# POWER.net
KiCad netlist of a schematic drawn in Altium Designer
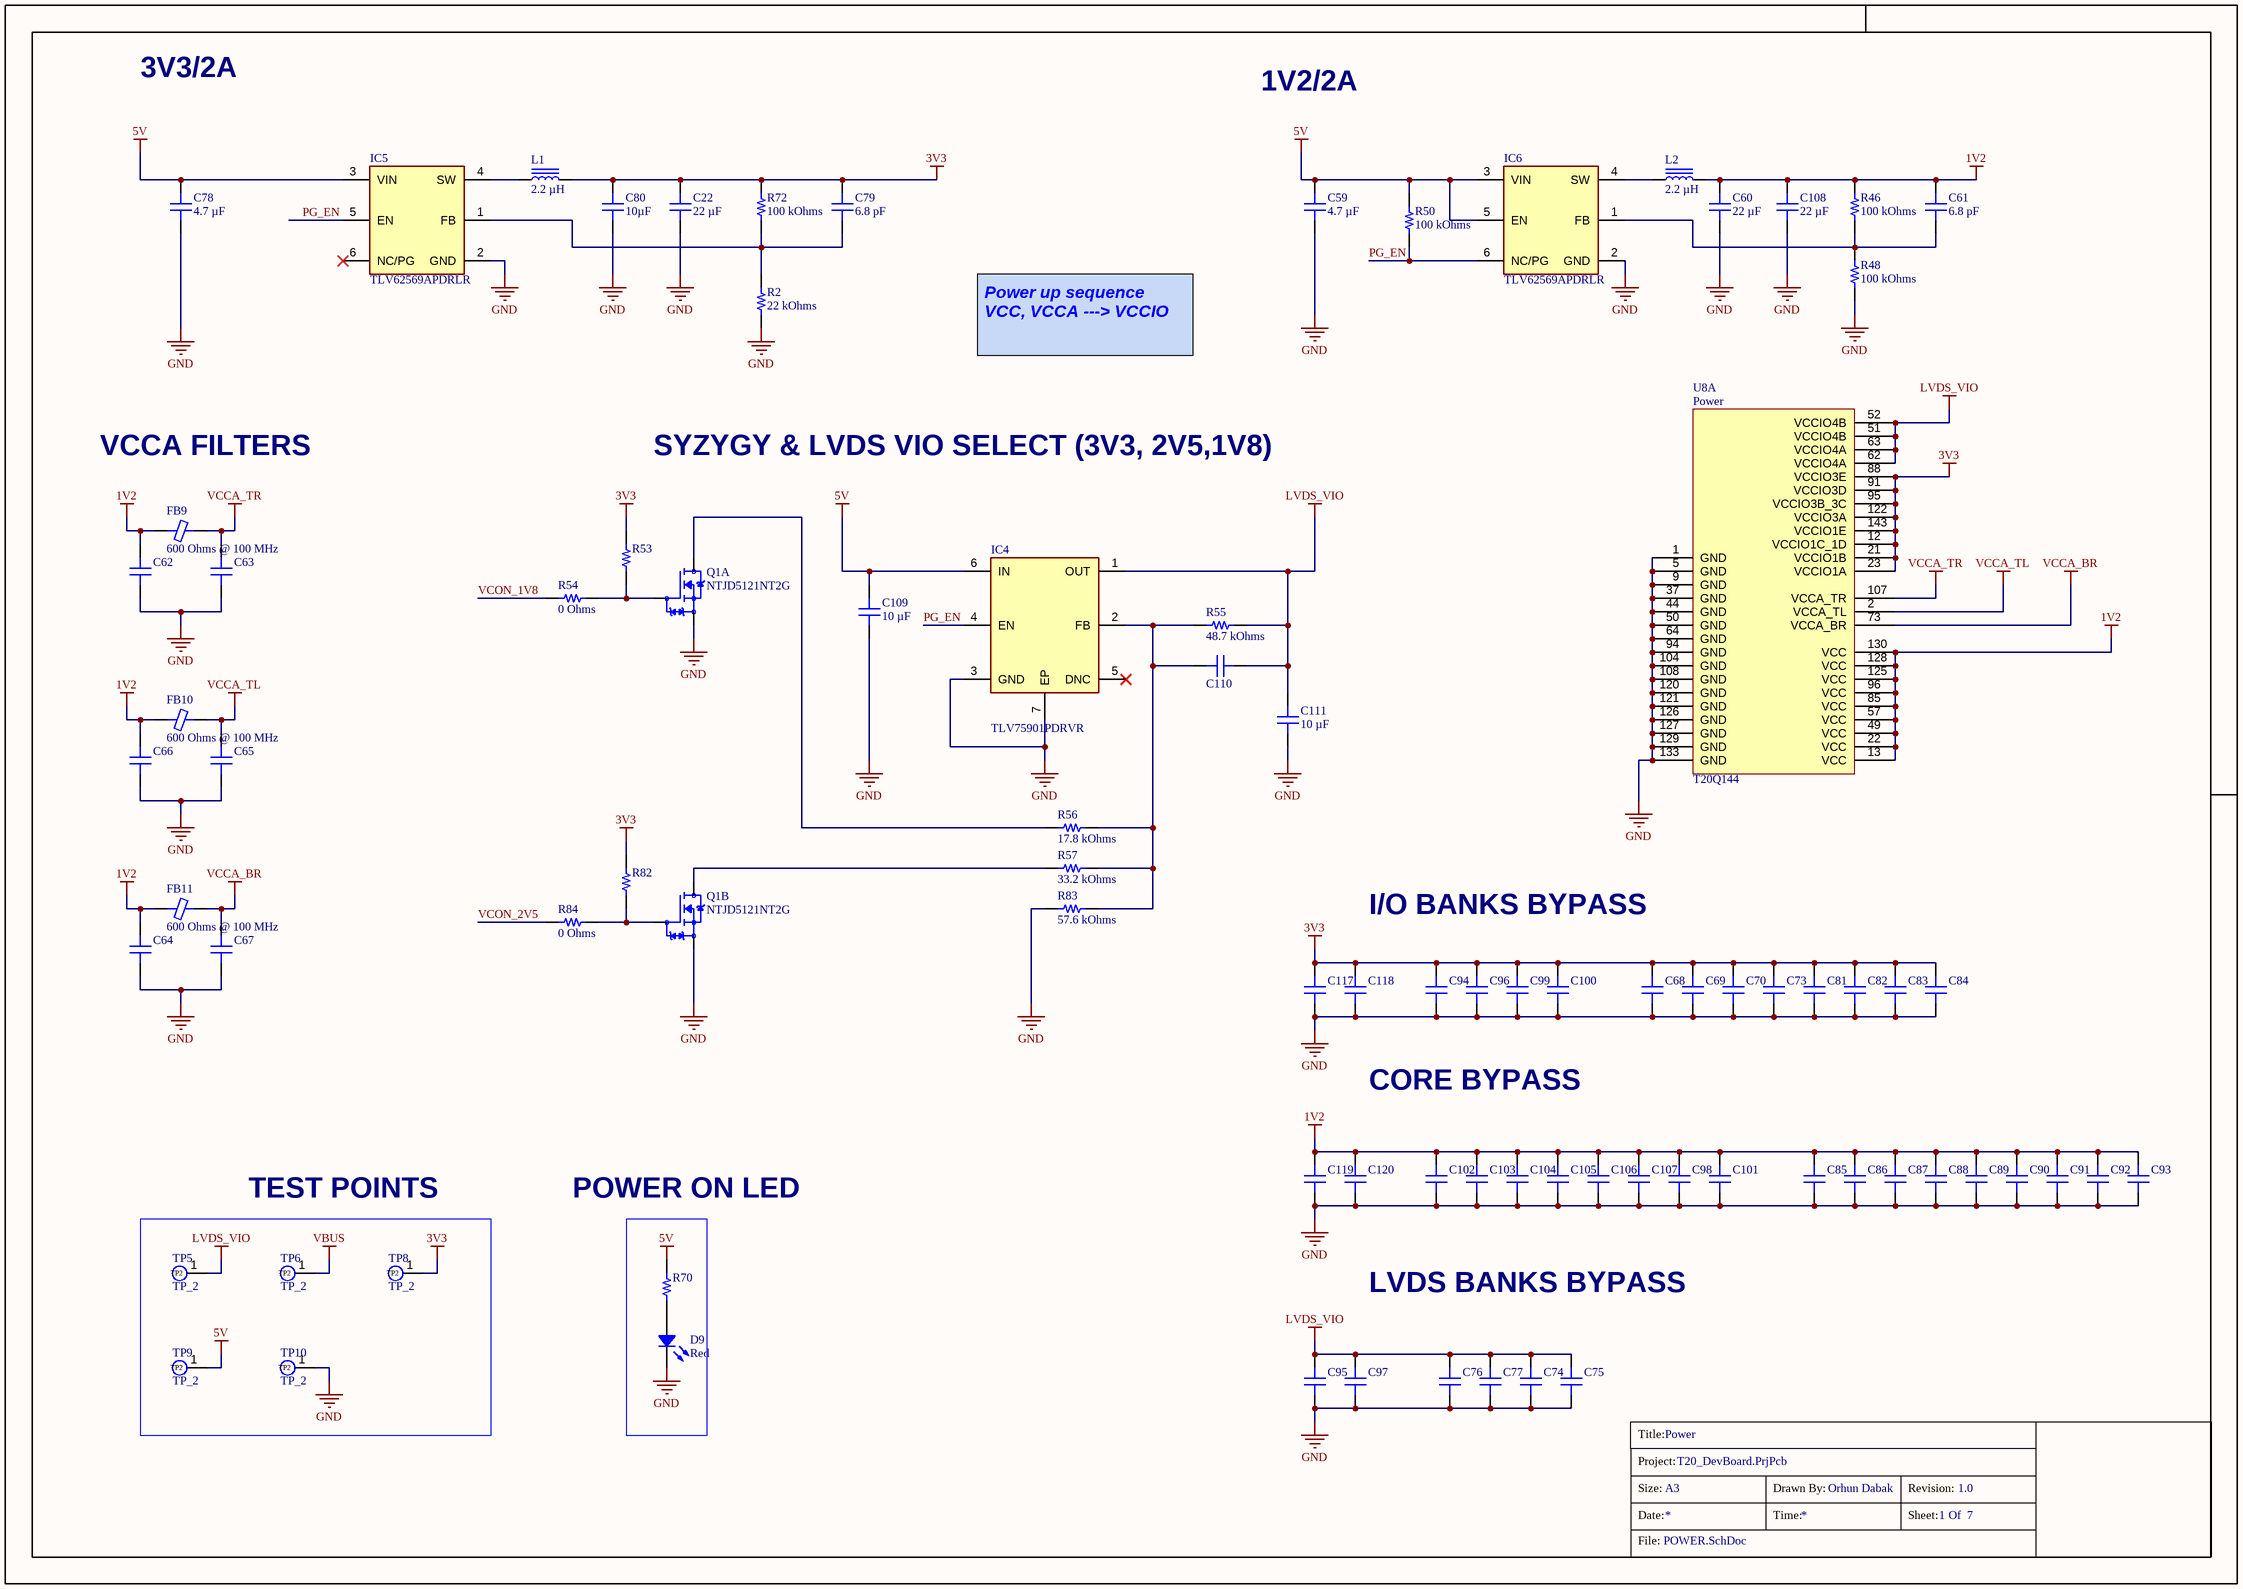
[diagram p0: POWER.SchDoc]

(export (version "E")
  (design (tool "Eeschema 10.0.6"))
  (components
    (comp (ref "C22")
      (value "22 µF")
      (footprint "CAP 0805_2012")
      (description "CAP CER 22UF 10V X5R 0805")
      (fields (field (name "PART NUMBER") "LMK212BJ226MG-T") (field (name "MANUFACTURER") "Taiyo Yuden"))
      (libsource (lib "Celestial Altium Library - altium_library") (part "Capacitor"))
    )
    (comp (ref "C59")
      (value "4.7 µF")
      (footprint "CAP 0805_2012")
      (description "CAP CER 4.7UF 25V X7R 0805")
      (fields
        (field (name "PART NUMBER") "CL21B475KAFNNNE")
        (field (name "MANUFACTURER") "Samsung Electro-Mechanics")
      )
      (libsource (lib "Celestial Altium Library - altium_library") (part "Capacitor"))
    )
    (comp (ref "C60")
      (value "22 µF")
      (footprint "CAP 0805_2012")
      (description "CAP CER 22UF 10V X5R 0805")
      (fields (field (name "PART NUMBER") "LMK212BJ226MG-T") (field (name "MANUFACTURER") "Taiyo Yuden"))
      (libsource (lib "Celestial Altium Library - altium_library") (part "Capacitor"))
    )
    (comp (ref "C61")
      (value "6.8 pF")
      (footprint "CAP 0402_1005")
      (description "CAP CER 6.8PF 16V C0G/NP0 0402")
      (fields (field (name "PART NUMBER") "885012005024") (field (name "MANUFACTURER") "Würth Elektronik"))
      (libsource (lib "Celestial Altium Library - altium_library") (part "Capacitor"))
    )
    (comp (ref "C62")
      (value "0.1 µF")
      (footprint "CAP 0402_1005")
      (description "CAP CER 0.1UF 10V X7R 0402")
      (fields (field (name "PART NUMBER") "CC0402KRX7R6BB104") (field (name "MANUFACTURER") "Yageo"))
      (libsource (lib "Celestial Altium Library - altium_library") (part "Capacitor"))
    )
    (comp (ref "C63")
      (value "0.1 µF")
      (footprint "CAP 0402_1005")
      (description "CAP CER 0.1UF 10V X7R 0402")
      (fields (field (name "PART NUMBER") "CC0402KRX7R6BB104") (field (name "MANUFACTURER") "Yageo"))
      (libsource (lib "Celestial Altium Library - altium_library") (part "Capacitor"))
    )
    (comp (ref "C64")
      (value "0.1 µF")
      (footprint "CAP 0402_1005")
      (description "CAP CER 0.1UF 10V X7R 0402")
      (fields (field (name "PART NUMBER") "CC0402KRX7R6BB104") (field (name "MANUFACTURER") "Yageo"))
      (libsource (lib "Celestial Altium Library - altium_library") (part "Capacitor"))
    )
    (comp (ref "C65")
      (value "0.1 µF")
      (footprint "CAP 0402_1005")
      (description "CAP CER 0.1UF 10V X7R 0402")
      (fields (field (name "PART NUMBER") "CC0402KRX7R6BB104") (field (name "MANUFACTURER") "Yageo"))
      (libsource (lib "Celestial Altium Library - altium_library") (part "Capacitor"))
    )
    (comp (ref "C66")
      (value "0.1 µF")
      (footprint "CAP 0402_1005")
      (description "CAP CER 0.1UF 10V X7R 0402")
      (fields (field (name "PART NUMBER") "CC0402KRX7R6BB104") (field (name "MANUFACTURER") "Yageo"))
      (libsource (lib "Celestial Altium Library - altium_library") (part "Capacitor"))
    )
    (comp (ref "C67")
      (value "0.1 µF")
      (footprint "CAP 0402_1005")
      (description "CAP CER 0.1UF 10V X7R 0402")
      (fields (field (name "PART NUMBER") "CC0402KRX7R6BB104") (field (name "MANUFACTURER") "Yageo"))
      (libsource (lib "Celestial Altium Library - altium_library") (part "Capacitor"))
    )
    (comp (ref "C68")
      (value "0.1 µF")
      (footprint "CAP 0402_1005")
      (description "CAP CER 0.1UF 10V X7R 0402")
      (fields (field (name "PART NUMBER") "CC0402KRX7R6BB104") (field (name "MANUFACTURER") "Yageo"))
      (libsource (lib "Celestial Altium Library - altium_library") (part "Capacitor"))
    )
    (comp (ref "C69")
      (value "0.1 µF")
      (footprint "CAP 0402_1005")
      (description "CAP CER 0.1UF 10V X7R 0402")
      (fields (field (name "PART NUMBER") "CC0402KRX7R6BB104") (field (name "MANUFACTURER") "Yageo"))
      (libsource (lib "Celestial Altium Library - altium_library") (part "Capacitor"))
    )
    (comp (ref "C70")
      (value "0.1 µF")
      (footprint "CAP 0402_1005")
      (description "CAP CER 0.1UF 10V X7R 0402")
      (fields (field (name "PART NUMBER") "CC0402KRX7R6BB104") (field (name "MANUFACTURER") "Yageo"))
      (libsource (lib "Celestial Altium Library - altium_library") (part "Capacitor"))
    )
    (comp (ref "C73")
      (value "0.1 µF")
      (footprint "CAP 0402_1005")
      (description "CAP CER 0.1UF 10V X7R 0402")
      (fields (field (name "PART NUMBER") "CC0402KRX7R6BB104") (field (name "MANUFACTURER") "Yageo"))
      (libsource (lib "Celestial Altium Library - altium_library") (part "Capacitor"))
    )
    (comp (ref "C74")
      (value "0.1 µF")
      (footprint "CAP 0402_1005")
      (description "CAP CER 0.1UF 10V X7R 0402")
      (fields (field (name "PART NUMBER") "CC0402KRX7R6BB104") (field (name "MANUFACTURER") "Yageo"))
      (libsource (lib "Celestial Altium Library - altium_library") (part "Capacitor"))
    )
    (comp (ref "C75")
      (value "0.1 µF")
      (footprint "CAP 0402_1005")
      (description "CAP CER 0.1UF 10V X7R 0402")
      (fields (field (name "PART NUMBER") "CC0402KRX7R6BB104") (field (name "MANUFACTURER") "Yageo"))
      (libsource (lib "Celestial Altium Library - altium_library") (part "Capacitor"))
    )
    (comp (ref "C76")
      (value "0.1 µF")
      (footprint "CAP 0402_1005")
      (description "CAP CER 0.1UF 10V X7R 0402")
      (fields (field (name "PART NUMBER") "CC0402KRX7R6BB104") (field (name "MANUFACTURER") "Yageo"))
      (libsource (lib "Celestial Altium Library - altium_library") (part "Capacitor"))
    )
    (comp (ref "C77")
      (value "0.1 µF")
      (footprint "CAP 0402_1005")
      (description "CAP CER 0.1UF 10V X7R 0402")
      (fields (field (name "PART NUMBER") "CC0402KRX7R6BB104") (field (name "MANUFACTURER") "Yageo"))
      (libsource (lib "Celestial Altium Library - altium_library") (part "Capacitor"))
    )
    (comp (ref "C78")
      (value "4.7 µF")
      (footprint "CAP 0805_2012")
      (description "CAP CER 4.7UF 25V X7R 0805")
      (fields
        (field (name "PART NUMBER") "CL21B475KAFNNNE")
        (field (name "MANUFACTURER") "Samsung Electro-Mechanics")
      )
      (libsource (lib "Celestial Altium Library - altium_library") (part "Capacitor"))
    )
    (comp (ref "C79")
      (value "6.8 pF")
      (footprint "CAP 0402_1005")
      (description "CAP CER 6.8PF 16V C0G/NP0 0402")
      (fields (field (name "PART NUMBER") "885012005024") (field (name "MANUFACTURER") "Würth Elektronik"))
      (libsource (lib "Celestial Altium Library - altium_library") (part "Capacitor"))
    )
    (comp (ref "C80")
      (value "10µF")
      (footprint "CAP 0805_2012")
      (description "CAP CER 10UF 10V X7R 0805")
      (fields (field (name "PART NUMBER") "0805ZC106MAT2A") (field (name "MANUFACTURER") "AVX Corporation"))
      (libsource (lib "Celestial Altium Library - altium_library") (part "Capacitor"))
    )
    (comp (ref "C81")
      (value "0.1 µF")
      (footprint "CAP 0402_1005")
      (description "CAP CER 0.1UF 10V X7R 0402")
      (fields (field (name "PART NUMBER") "CC0402KRX7R6BB104") (field (name "MANUFACTURER") "Yageo"))
      (libsource (lib "Celestial Altium Library - altium_library") (part "Capacitor"))
    )
    (comp (ref "C82")
      (value "0.1 µF")
      (footprint "CAP 0402_1005")
      (description "CAP CER 0.1UF 10V X7R 0402")
      (fields (field (name "PART NUMBER") "CC0402KRX7R6BB104") (field (name "MANUFACTURER") "Yageo"))
      (libsource (lib "Celestial Altium Library - altium_library") (part "Capacitor"))
    )
    (comp (ref "C83")
      (value "0.1 µF")
      (footprint "CAP 0402_1005")
      (description "CAP CER 0.1UF 10V X7R 0402")
      (fields (field (name "PART NUMBER") "CC0402KRX7R6BB104") (field (name "MANUFACTURER") "Yageo"))
      (libsource (lib "Celestial Altium Library - altium_library") (part "Capacitor"))
    )
    (comp (ref "C84")
      (value "0.1 µF")
      (footprint "CAP 0402_1005")
      (description "CAP CER 0.1UF 10V X7R 0402")
      (fields (field (name "PART NUMBER") "CC0402KRX7R6BB104") (field (name "MANUFACTURER") "Yageo"))
      (libsource (lib "Celestial Altium Library - altium_library") (part "Capacitor"))
    )
    (comp (ref "C85")
      (value "0.1 µF")
      (footprint "CAP 0402_1005")
      (description "CAP CER 0.1UF 10V X7R 0402")
      (fields (field (name "PART NUMBER") "CC0402KRX7R6BB104") (field (name "MANUFACTURER") "Yageo"))
      (libsource (lib "Celestial Altium Library - altium_library") (part "Capacitor"))
    )
    (comp (ref "C86")
      (value "0.1 µF")
      (footprint "CAP 0402_1005")
      (description "CAP CER 0.1UF 10V X7R 0402")
      (fields (field (name "PART NUMBER") "CC0402KRX7R6BB104") (field (name "MANUFACTURER") "Yageo"))
      (libsource (lib "Celestial Altium Library - altium_library") (part "Capacitor"))
    )
    (comp (ref "C87")
      (value "0.1 µF")
      (footprint "CAP 0402_1005")
      (description "CAP CER 0.1UF 10V X7R 0402")
      (fields (field (name "PART NUMBER") "CC0402KRX7R6BB104") (field (name "MANUFACTURER") "Yageo"))
      (libsource (lib "Celestial Altium Library - altium_library") (part "Capacitor"))
    )
    (comp (ref "C88")
      (value "0.1 µF")
      (footprint "CAP 0402_1005")
      (description "CAP CER 0.1UF 10V X7R 0402")
      (fields (field (name "PART NUMBER") "CC0402KRX7R6BB104") (field (name "MANUFACTURER") "Yageo"))
      (libsource (lib "Celestial Altium Library - altium_library") (part "Capacitor"))
    )
    (comp (ref "C89")
      (value "0.1 µF")
      (footprint "CAP 0402_1005")
      (description "CAP CER 0.1UF 10V X7R 0402")
      (fields (field (name "PART NUMBER") "CC0402KRX7R6BB104") (field (name "MANUFACTURER") "Yageo"))
      (libsource (lib "Celestial Altium Library - altium_library") (part "Capacitor"))
    )
    (comp (ref "C90")
      (value "0.1 µF")
      (footprint "CAP 0402_1005")
      (description "CAP CER 0.1UF 10V X7R 0402")
      (fields (field (name "PART NUMBER") "CC0402KRX7R6BB104") (field (name "MANUFACTURER") "Yageo"))
      (libsource (lib "Celestial Altium Library - altium_library") (part "Capacitor"))
    )
    (comp (ref "C91")
      (value "0.1 µF")
      (footprint "CAP 0402_1005")
      (description "CAP CER 0.1UF 10V X7R 0402")
      (fields (field (name "PART NUMBER") "CC0402KRX7R6BB104") (field (name "MANUFACTURER") "Yageo"))
      (libsource (lib "Celestial Altium Library - altium_library") (part "Capacitor"))
    )
    (comp (ref "C92")
      (value "0.1 µF")
      (footprint "CAP 0402_1005")
      (description "CAP CER 0.1UF 10V X7R 0402")
      (fields (field (name "PART NUMBER") "CC0402KRX7R6BB104") (field (name "MANUFACTURER") "Yageo"))
      (libsource (lib "Celestial Altium Library - altium_library") (part "Capacitor"))
    )
    (comp (ref "C93")
      (value "0.1 µF")
      (footprint "CAP 0402_1005")
      (description "CAP CER 0.1UF 10V X7R 0402")
      (fields (field (name "PART NUMBER") "CC0402KRX7R6BB104") (field (name "MANUFACTURER") "Yageo"))
      (libsource (lib "Celestial Altium Library - altium_library") (part "Capacitor"))
    )
    (comp (ref "C94")
      (value "1 µF")
      (footprint "CAP 0402_1005")
      (description "CAP CER 1UF 6.3V X7R 0402")
      (fields
        (field (name "PART NUMBER") "GRM155R70J105KA12J")
        (field (name "MANUFACTURER") "Murata Electronics")
      )
      (libsource (lib "Celestial Altium Library - altium_library") (part "Capacitor"))
    )
    (comp (ref "C95")
      (value "1 µF")
      (footprint "CAP 0402_1005")
      (description "CAP CER 1UF 6.3V X7R 0402")
      (fields
        (field (name "PART NUMBER") "GRM155R70J105KA12J")
        (field (name "MANUFACTURER") "Murata Electronics")
      )
      (libsource (lib "Celestial Altium Library - altium_library") (part "Capacitor"))
    )
    (comp (ref "C96")
      (value "1 µF")
      (footprint "CAP 0402_1005")
      (description "CAP CER 1UF 6.3V X7R 0402")
      (fields
        (field (name "PART NUMBER") "GRM155R70J105KA12J")
        (field (name "MANUFACTURER") "Murata Electronics")
      )
      (libsource (lib "Celestial Altium Library - altium_library") (part "Capacitor"))
    )
    (comp (ref "C97")
      (value "1 µF")
      (footprint "CAP 0402_1005")
      (description "CAP CER 1UF 6.3V X7R 0402")
      (fields
        (field (name "PART NUMBER") "GRM155R70J105KA12J")
        (field (name "MANUFACTURER") "Murata Electronics")
      )
      (libsource (lib "Celestial Altium Library - altium_library") (part "Capacitor"))
    )
    (comp (ref "C98")
      (value "1 µF")
      (footprint "CAP 0402_1005")
      (description "CAP CER 1UF 6.3V X7R 0402")
      (fields
        (field (name "PART NUMBER") "GRM155R70J105KA12J")
        (field (name "MANUFACTURER") "Murata Electronics")
      )
      (libsource (lib "Celestial Altium Library - altium_library") (part "Capacitor"))
    )
    (comp (ref "C99")
      (value "1 µF")
      (footprint "CAP 0402_1005")
      (description "CAP CER 1UF 6.3V X7R 0402")
      (fields
        (field (name "PART NUMBER") "GRM155R70J105KA12J")
        (field (name "MANUFACTURER") "Murata Electronics")
      )
      (libsource (lib "Celestial Altium Library - altium_library") (part "Capacitor"))
    )
    (comp (ref "C100")
      (value "1 µF")
      (footprint "CAP 0402_1005")
      (description "CAP CER 1UF 6.3V X7R 0402")
      (fields
        (field (name "PART NUMBER") "GRM155R70J105KA12J")
        (field (name "MANUFACTURER") "Murata Electronics")
      )
      (libsource (lib "Celestial Altium Library - altium_library") (part "Capacitor"))
    )
    (comp (ref "C101")
      (value "1 µF")
      (footprint "CAP 0402_1005")
      (description "CAP CER 1UF 6.3V X7R 0402")
      (fields
        (field (name "PART NUMBER") "GRM155R70J105KA12J")
        (field (name "MANUFACTURER") "Murata Electronics")
      )
      (libsource (lib "Celestial Altium Library - altium_library") (part "Capacitor"))
    )
    (comp (ref "C102")
      (value "1 µF")
      (footprint "CAP 0402_1005")
      (description "CAP CER 1UF 6.3V X7R 0402")
      (fields
        (field (name "PART NUMBER") "GRM155R70J105KA12J")
        (field (name "MANUFACTURER") "Murata Electronics")
      )
      (libsource (lib "Celestial Altium Library - altium_library") (part "Capacitor"))
    )
    (comp (ref "C103")
      (value "1 µF")
      (footprint "CAP 0402_1005")
      (description "CAP CER 1UF 6.3V X7R 0402")
      (fields
        (field (name "PART NUMBER") "GRM155R70J105KA12J")
        (field (name "MANUFACTURER") "Murata Electronics")
      )
      (libsource (lib "Celestial Altium Library - altium_library") (part "Capacitor"))
    )
    (comp (ref "C104")
      (value "1 µF")
      (footprint "CAP 0402_1005")
      (description "CAP CER 1UF 6.3V X7R 0402")
      (fields
        (field (name "PART NUMBER") "GRM155R70J105KA12J")
        (field (name "MANUFACTURER") "Murata Electronics")
      )
      (libsource (lib "Celestial Altium Library - altium_library") (part "Capacitor"))
    )
    (comp (ref "C105")
      (value "1 µF")
      (footprint "CAP 0402_1005")
      (description "CAP CER 1UF 6.3V X7R 0402")
      (fields
        (field (name "PART NUMBER") "GRM155R70J105KA12J")
        (field (name "MANUFACTURER") "Murata Electronics")
      )
      (libsource (lib "Celestial Altium Library - altium_library") (part "Capacitor"))
    )
    (comp (ref "C106")
      (value "1 µF")
      (footprint "CAP 0402_1005")
      (description "CAP CER 1UF 6.3V X7R 0402")
      (fields
        (field (name "PART NUMBER") "GRM155R70J105KA12J")
        (field (name "MANUFACTURER") "Murata Electronics")
      )
      (libsource (lib "Celestial Altium Library - altium_library") (part "Capacitor"))
    )
    (comp (ref "C107")
      (value "1 µF")
      (footprint "CAP 0402_1005")
      (description "CAP CER 1UF 6.3V X7R 0402")
      (fields
        (field (name "PART NUMBER") "GRM155R70J105KA12J")
        (field (name "MANUFACTURER") "Murata Electronics")
      )
      (libsource (lib "Celestial Altium Library - altium_library") (part "Capacitor"))
    )
    (comp (ref "C108")
      (value "22 µF")
      (footprint "CAP 0805_2012")
      (description "CAP CER 22UF 10V X5R 0805")
      (fields (field (name "PART NUMBER") "LMK212BJ226MG-T") (field (name "MANUFACTURER") "Taiyo Yuden"))
      (libsource (lib "Celestial Altium Library - altium_library") (part "Capacitor"))
    )
    (comp (ref "C109")
      (value "10 µF")
      (footprint "CAP 0603_1608")
      (description "CAP CER 10UF 6.3V X5R 0603")
      (fields
        (field (name "PART NUMBER") "GRM188R60J106ME47D")
        (field (name "MANUFACTURER") "Murata Electronics")
      )
      (libsource (lib "Celestial Altium Library - altium_library") (part "Capacitor"))
    )
    (comp (ref "C110")
      (value "0.1 µF")
      (footprint "CAP 0402_1005")
      (description "CAP CER 0.1UF 10V X7R 0402")
      (fields (field (name "PART NUMBER") "CC0402KRX7R6BB104") (field (name "MANUFACTURER") "Yageo"))
      (libsource (lib "Celestial Altium Library - altium_library") (part "Capacitor"))
    )
    (comp (ref "C111")
      (value "10 µF")
      (footprint "CAP 0603_1608")
      (description "CAP CER 10UF 6.3V X5R 0603")
      (fields
        (field (name "PART NUMBER") "GRM188R60J106ME47D")
        (field (name "MANUFACTURER") "Murata Electronics")
      )
      (libsource (lib "Celestial Altium Library - altium_library") (part "Capacitor"))
    )
    (comp (ref "C117")
      (value "10 µF")
      (footprint "CAP 0603_1608")
      (description "CAP CER 10UF 6.3V X5R 0603")
      (fields
        (field (name "PART NUMBER") "GRM188R60J106KE47D")
        (field (name "MANUFACTURER") "Murata Electronics")
      )
      (libsource (lib "Celestial Altium Library - altium_library") (part "Capacitor"))
    )
    (comp (ref "C118")
      (value "10 µF")
      (footprint "CAP 0603_1608")
      (description "CAP CER 10UF 6.3V X5R 0603")
      (fields
        (field (name "PART NUMBER") "GRM188R60J106KE47D")
        (field (name "MANUFACTURER") "Murata Electronics")
      )
      (libsource (lib "Celestial Altium Library - altium_library") (part "Capacitor"))
    )
    (comp (ref "C119")
      (value "10 µF")
      (footprint "CAP 0603_1608")
      (description "CAP CER 10UF 6.3V X5R 0603")
      (fields
        (field (name "PART NUMBER") "GRM188R60J106KE47D")
        (field (name "MANUFACTURER") "Murata Electronics")
      )
      (libsource (lib "Celestial Altium Library - altium_library") (part "Capacitor"))
    )
    (comp (ref "C120")
      (value "10 µF")
      (footprint "CAP 0603_1608")
      (description "CAP CER 10UF 6.3V X5R 0603")
      (fields
        (field (name "PART NUMBER") "GRM188R60J106KE47D")
        (field (name "MANUFACTURER") "Murata Electronics")
      )
      (libsource (lib "Celestial Altium Library - altium_library") (part "Capacitor"))
    )
    (comp (ref "D9")
      (value "Red")
      (footprint "LED 0603_1608 RED")
      (description "LED RED CLEAR CHIP SMD")
      (fields (field (name "PART NUMBER") "LTST-C193KRKT-2A") (field (name "MANUFACTURER") "Lite-On Inc."))
      (libsource (lib "Celestial Altium Library - altium_library") (part "LED"))
    )
    (comp (ref "FB9")
      (value "600 Ohms @ 100 MHz")
      (footprint "FER 0402_1005")
      (description "FERRITE BEAD 600 OHM 0402 1LN")
      (fields
        (field (name "PART NUMBER") "BLM15AG601SN1D")
        (field (name "MANUFACTURER") "Murata Electronics")
      )
      (libsource (lib "Celestial Altium Library - altium_library") (part "Ferrite Chip"))
    )
    (comp (ref "FB10")
      (value "600 Ohms @ 100 MHz")
      (footprint "FER 0402_1005")
      (description "FERRITE BEAD 600 OHM 0402 1LN")
      (fields
        (field (name "PART NUMBER") "BLM15AG601SN1D")
        (field (name "MANUFACTURER") "Murata Electronics")
      )
      (libsource (lib "Celestial Altium Library - altium_library") (part "Ferrite Chip"))
    )
    (comp (ref "FB11")
      (value "600 Ohms @ 100 MHz")
      (footprint "FER 0402_1005")
      (description "FERRITE BEAD 600 OHM 0402 1LN")
      (fields
        (field (name "PART NUMBER") "BLM15AG601SN1D")
        (field (name "MANUFACTURER") "Murata Electronics")
      )
      (libsource (lib "Celestial Altium Library - altium_library") (part "Ferrite Chip"))
    )
    (comp (ref "IC4")
      (value "TLV75901PDRVR")
      (footprint "SamacSys:SON65P200X200X80-7N")
      (description "Integrated Circuit")
      (fields (field (name "MOUSER PART NUMBER") "595-TLV75901PDRVR"))
      (libsource (lib "SamacSys") (part "TLV75901PDRVR"))
    )
    (comp (ref "IC5")
      (value "TLV62569APDRLR")
      (footprint "SamacSys:SOTFL50P160X60-6N")
      (description "Integrated Circuit")
      (fields (field (name "MOUSER PART NUMBER") "595-TLV62569APDRLR"))
      (libsource (lib "SamacSys") (part "TLV62569APDRLR"))
    )
    (comp (ref "IC6")
      (value "TLV62569APDRLR")
      (footprint "SamacSys:SOTFL50P160X60-6N")
      (description "Integrated Circuit")
      (fields (field (name "MOUSER PART NUMBER") "595-TLV62569APDRLR"))
      (libsource (lib "SamacSys") (part "TLV62569APDRLR"))
    )
    (comp (ref "L1")
      (value "2.2 µH")
      (footprint "TDK VLS252012HBX-1")
      (description "FIXED IND 2.2UH 2.3A 102MOHM SMD")
      (fields
        (field (name "PART NUMBER") "VLS252012HBX-2R2M-1")
        (field (name "MANUFACTURER") "TDK Corporation")
      )
      (libsource (lib "Celestial Altium Library - altium_library") (part "Inductor"))
    )
    (comp (ref "L2")
      (value "2.2 µH")
      (footprint "TDK VLS252012HBX-1")
      (description "FIXED IND 2.2UH 2.3A 102MOHM SMD")
      (fields
        (field (name "PART NUMBER") "VLS252012HBX-2R2M-1")
        (field (name "MANUFACTURER") "TDK Corporation")
      )
      (libsource (lib "Celestial Altium Library - altium_library") (part "Inductor"))
    )
    (comp (ref "Q1")
      (value "NTJD5121NT2G")
      (footprint "SOT65P210X110-6N:SOT65P210X110-6N")
      (description "Mosfet Array 2 N-Channel (Dual) 60V 295mA 250mW Surface Mount SC-88/SC70-6/SOT-363")
      (fields (field (name "MF") "ON Semiconductor"))
      (libsource (lib "NTJD5121NT2G") (part "NTJD5121NT2G"))
    )
    (comp (ref "R2")
      (value "22 kOhms")
      (footprint "RES 0402_1005")
      (description "RES 22K OHM 1% 1/16W 0402")
      (fields
        (field (name "PART NUMBER") "RMCF0402FT22K0")
        (field (name "MANUFACTURER") "Stackpole Electronics Inc")
      )
      (libsource (lib "Celestial Altium Library - altium_library") (part "Resistor"))
    )
    (comp (ref "R46")
      (value "100 kOhms")
      (footprint "RES 0402_1005")
      (description "RES SMD 100K OHM 1% 1/16W 0402")
      (fields (field (name "PART NUMBER") "AC0402FR-07100KL") (field (name "MANUFACTURER") "Yageo"))
      (libsource (lib "Celestial Altium Library - altium_library") (part "Resistor"))
    )
    (comp (ref "R48")
      (value "100 kOhms")
      (footprint "RES 0402_1005")
      (description "RES SMD 100K OHM 1% 1/16W 0402")
      (fields (field (name "PART NUMBER") "AC0402FR-07100KL") (field (name "MANUFACTURER") "Yageo"))
      (libsource (lib "Celestial Altium Library - altium_library") (part "Resistor"))
    )
    (comp (ref "R50")
      (value "100 kOhms")
      (footprint "RES 0402_1005")
      (description "RES SMD 100K OHM 1% 1/16W 0402")
      (fields (field (name "PART NUMBER") "RT0402FRE07100KL") (field (name "MANUFACTURER") "Yageo"))
      (libsource (lib "Celestial Altium Library - altium_library") (part "Resistor"))
    )
    (comp (ref "R53")
      (value "10 kOhms")
      (footprint "RES 0402_1005")
      (description "RES 10K OHM 0.1% 1/10W 0402")
      (fields
        (field (name "PART NUMBER") "RP73PF1E10KBTD")
        (field (name "MANUFACTURER") "TE Connectivity Passive Product")
      )
      (libsource (lib "Celestial Altium Library - altium_library") (part "Resistor"))
    )
    (comp (ref "R54")
      (value "0 Ohms")
      (footprint "RES 0402_1005")
      (description "RES 0 OHM JUMPER 1/16W 0402")
      (fields (field (name "PART NUMBER") "RC0402JR-070RL") (field (name "MANUFACTURER") "Yageo"))
      (libsource (lib "Celestial Altium Library - altium_library") (part "Resistor"))
    )
    (comp (ref "R55")
      (value "48.7 kOhms")
      (footprint "RES 0402_1005")
      (description "RES SMD 48.7K OHM 1% 1/10W 0402")
      (fields
        (field (name "PART NUMBER") "ERJ-2RKF4872X")
        (field (name "MANUFACTURER") "Panasonic Electronic Components")
      )
      (libsource (lib "Celestial Altium Library - altium_library") (part "Resistor"))
    )
    (comp (ref "R56")
      (value "17.8 kOhms")
      (footprint "RES 0402_1005")
      (description "RES 17.8K OHM 1% 1/16W 0402")
      (fields (field (name "PART NUMBER") "RC0402FR-0717K8L") (field (name "MANUFACTURER") "Yageo"))
      (libsource (lib "Celestial Altium Library - altium_library") (part "Resistor"))
    )
    (comp (ref "R57")
      (value "33.2 kOhms")
      (footprint "RES 0402_1005")
      (description "RES 33.2K OHM 1% 1/16W 0402")
      (fields (field (name "PART NUMBER") "RC0402FR-0733K2L") (field (name "MANUFACTURER") "Yageo"))
      (libsource (lib "Celestial Altium Library - altium_library") (part "Resistor"))
    )
    (comp (ref "R70")
      (value "1 kOhms")
      (footprint "RES 0402_1005")
      (description "RES SMD 1K OHM 1% 1/16W 0402")
      (fields (field (name "PART NUMBER") "AC0402FR-071KL") (field (name "MANUFACTURER") "Yageo"))
      (libsource (lib "Celestial Altium Library - altium_library") (part "Resistor"))
    )
    (comp (ref "R72")
      (value "100 kOhms")
      (footprint "RES 0402_1005")
      (description "RES SMD 100K OHM 1% 1/16W 0402")
      (fields (field (name "PART NUMBER") "AC0402FR-07100KL") (field (name "MANUFACTURER") "Yageo"))
      (libsource (lib "Celestial Altium Library - altium_library") (part "Resistor"))
    )
    (comp (ref "R82")
      (value "10 kOhms")
      (footprint "RES 0402_1005")
      (description "RES 10K OHM 0.1% 1/10W 0402")
      (fields
        (field (name "PART NUMBER") "RP73PF1E10KBTD")
        (field (name "MANUFACTURER") "TE Connectivity Passive Product")
      )
      (libsource (lib "Celestial Altium Library - altium_library") (part "Resistor"))
    )
    (comp (ref "R83")
      (value "57.6 kOhms")
      (footprint "RES 0402_1005")
      (description "RES SMD 57.6K OHM 1% 1/10W 0402")
      (fields
        (field (name "PART NUMBER") "ERJ-2RKF5762X")
        (field (name "MANUFACTURER") "Panasonic Electronic Components")
      )
      (libsource (lib "Celestial Altium Library - altium_library") (part "Resistor"))
    )
    (comp (ref "R84")
      (value "0 Ohms")
      (footprint "RES 0402_1005")
      (description "RES 0 OHM JUMPER 1/16W 0402")
      (fields (field (name "PART NUMBER") "RC0402JR-070RL") (field (name "MANUFACTURER") "Yageo"))
      (libsource (lib "Celestial Altium Library - altium_library") (part "Resistor"))
    )
    (comp (ref "TP5")
      (value "TP_2")
      (footprint "TEST POINT")
      (description "1.5x1.5mm Test Point")
      (libsource (lib "FPGA_Based_SOM") (part "TEST POINT_2"))
    )
    (comp (ref "TP6")
      (value "TP_2")
      (footprint "TEST POINT")
      (description "1.5x1.5mm Test Point")
      (libsource (lib "FPGA_Based_SOM") (part "TEST POINT_2"))
    )
    (comp (ref "TP8")
      (value "TP_2")
      (footprint "TEST POINT")
      (description "1.5x1.5mm Test Point")
      (libsource (lib "FPGA_Based_SOM") (part "TEST POINT_2"))
    )
    (comp (ref "TP9")
      (value "TP_2")
      (footprint "TEST POINT")
      (description "1.5x1.5mm Test Point")
      (libsource (lib "FPGA_Based_SOM") (part "TEST POINT_2"))
    )
    (comp (ref "TP10")
      (value "TP_2")
      (footprint "TEST POINT")
      (description "1.5x1.5mm Test Point")
      (libsource (lib "FPGA_Based_SOM") (part "TEST POINT_2"))
    )
    (comp (ref "U8")
      (value "T20Q144")
      (footprint "T8_devkit_PCB:CQFP50P2200X2200X160-144N")
      (description "Trion® Field Programmable Gate Array (FPGA) IC 97 1044 19728 144-LQFP")
      (libsource (lib "T8_devkit_PCB") (part "T20Q144"))
    )
  )
  (nets
    (net (code "1") (name "/PG_EN") (class "Default")
      (node (ref "IC4") (pin "4") (pinfunction "EN_4") (pintype "passive"))
      (node (ref "IC5") (pin "5") (pinfunction "EN_5") (pintype "passive"))
      (node (ref "IC6") (pin "6") (pinfunction "NC/PG_6") (pintype "passive"))
      (node (ref "R50") (pin "1") (pinfunction "1_1") (pintype "passive"))
    )
    (net (code "2") (name "/VCON_1V8") (class "Default")
      (node (ref "R54") (pin "1") (pinfunction "1_1") (pintype "passive"))
    )
    (net (code "3") (name "/VCON_2V5") (class "Default")
      (node (ref "R84") (pin "1") (pinfunction "1_1") (pintype "passive"))
    )
    (net (code "4") (name "1V2") (class "Default")
      (node (ref "C101") (pin "2") (pinfunction "2_2") (pintype "passive"))
      (node (ref "C102") (pin "2") (pinfunction "2_2") (pintype "passive"))
      (node (ref "C103") (pin "2") (pinfunction "2_2") (pintype "passive"))
      (node (ref "C104") (pin "2") (pinfunction "2_2") (pintype "passive"))
      (node (ref "C105") (pin "2") (pinfunction "2_2") (pintype "passive"))
      (node (ref "C106") (pin "2") (pinfunction "2_2") (pintype "passive"))
      (node (ref "C107") (pin "2") (pinfunction "2_2") (pintype "passive"))
      (node (ref "C108") (pin "2") (pinfunction "2_2") (pintype "passive"))
      (node (ref "C119") (pin "2") (pinfunction "2_2") (pintype "passive"))
      (node (ref "C120") (pin "2") (pinfunction "2_2") (pintype "passive"))
      (node (ref "C60") (pin "2") (pinfunction "2_2") (pintype "passive"))
      (node (ref "C61") (pin "2") (pinfunction "2_2") (pintype "passive"))
      (node (ref "C62") (pin "2") (pinfunction "2_2") (pintype "passive"))
      (node (ref "C64") (pin "2") (pinfunction "2_2") (pintype "passive"))
      (node (ref "C66") (pin "2") (pinfunction "2_2") (pintype "passive"))
      (node (ref "C85") (pin "2") (pinfunction "2_2") (pintype "passive"))
      (node (ref "C86") (pin "2") (pinfunction "2_2") (pintype "passive"))
      (node (ref "C87") (pin "2") (pinfunction "2_2") (pintype "passive"))
      (node (ref "C88") (pin "2") (pinfunction "2_2") (pintype "passive"))
      (node (ref "C89") (pin "2") (pinfunction "2_2") (pintype "passive"))
      (node (ref "C90") (pin "2") (pinfunction "2_2") (pintype "passive"))
      (node (ref "C91") (pin "2") (pinfunction "2_2") (pintype "passive"))
      (node (ref "C92") (pin "2") (pinfunction "2_2") (pintype "passive"))
      (node (ref "C93") (pin "2") (pinfunction "2_2") (pintype "passive"))
      (node (ref "C98") (pin "2") (pinfunction "2_2") (pintype "passive"))
      (node (ref "FB10") (pin "1") (pinfunction "1_1") (pintype "passive"))
      (node (ref "FB11") (pin "1") (pinfunction "1_1") (pintype "passive"))
      (node (ref "FB9") (pin "1") (pinfunction "1_1") (pintype "passive"))
      (node (ref "L2") (pin "2") (pinfunction "2_2") (pintype "passive"))
      (node (ref "R46") (pin "2") (pinfunction "2_2") (pintype "passive"))
      (node (ref "U8") (pin "125") (pinfunction "VCC_125") (pintype "passive"))
      (node (ref "U8") (pin "128") (pinfunction "VCC_128") (pintype "passive"))
      (node (ref "U8") (pin "13") (pinfunction "VCC_13") (pintype "passive"))
      (node (ref "U8") (pin "130") (pinfunction "VCC_130") (pintype "passive"))
      (node (ref "U8") (pin "22") (pinfunction "VCC_22") (pintype "passive"))
      (node (ref "U8") (pin "49") (pinfunction "VCC_49") (pintype "passive"))
      (node (ref "U8") (pin "57") (pinfunction "VCC_57") (pintype "passive"))
      (node (ref "U8") (pin "85") (pinfunction "VCC_85") (pintype "passive"))
      (node (ref "U8") (pin "96") (pinfunction "VCC_96") (pintype "passive"))
    )
    (net (code "5") (name "3V3") (class "Default")
      (node (ref "C100") (pin "2") (pinfunction "2_2") (pintype "passive"))
      (node (ref "C117") (pin "2") (pinfunction "2_2") (pintype "passive"))
      (node (ref "C118") (pin "2") (pinfunction "2_2") (pintype "passive"))
      (node (ref "C22") (pin "2") (pinfunction "2_2") (pintype "passive"))
      (node (ref "C68") (pin "2") (pinfunction "2_2") (pintype "passive"))
      (node (ref "C69") (pin "2") (pinfunction "2_2") (pintype "passive"))
      (node (ref "C70") (pin "2") (pinfunction "2_2") (pintype "passive"))
      (node (ref "C73") (pin "2") (pinfunction "2_2") (pintype "passive"))
      (node (ref "C79") (pin "2") (pinfunction "2_2") (pintype "passive"))
      (node (ref "C80") (pin "2") (pinfunction "2_2") (pintype "passive"))
      (node (ref "C81") (pin "2") (pinfunction "2_2") (pintype "passive"))
      (node (ref "C82") (pin "2") (pinfunction "2_2") (pintype "passive"))
      (node (ref "C83") (pin "2") (pinfunction "2_2") (pintype "passive"))
      (node (ref "C84") (pin "2") (pinfunction "2_2") (pintype "passive"))
      (node (ref "C94") (pin "2") (pinfunction "2_2") (pintype "passive"))
      (node (ref "C96") (pin "2") (pinfunction "2_2") (pintype "passive"))
      (node (ref "C99") (pin "2") (pinfunction "2_2") (pintype "passive"))
      (node (ref "L1") (pin "2") (pinfunction "2_2") (pintype "passive"))
      (node (ref "R53") (pin "2") (pinfunction "2_2") (pintype "passive"))
      (node (ref "R72") (pin "2") (pinfunction "2_2") (pintype "passive"))
      (node (ref "R82") (pin "2") (pinfunction "2_2") (pintype "passive"))
      (node (ref "TP8") (pin "1") (pinfunction "TP2_1") (pintype "passive"))
      (node (ref "U8") (pin "12") (pinfunction "VCCIO1C_1D_12") (pintype "passive"))
      (node (ref "U8") (pin "122") (pinfunction "VCCIO3A_122") (pintype "passive"))
      (node (ref "U8") (pin "143") (pinfunction "VCCIO1E_143") (pintype "passive"))
      (node (ref "U8") (pin "21") (pinfunction "VCCIO1B_21") (pintype "passive"))
      (node (ref "U8") (pin "23") (pinfunction "VCCIO1A_23") (pintype "passive"))
      (node (ref "U8") (pin "88") (pinfunction "VCCIO3E_88") (pintype "passive"))
      (node (ref "U8") (pin "91") (pinfunction "VCCIO3D_91") (pintype "passive"))
      (node (ref "U8") (pin "95") (pinfunction "VCCIO3B_3C_95") (pintype "passive"))
    )
    (net (code "6") (name "5V") (class "Default")
      (node (ref "C109") (pin "2") (pinfunction "2_2") (pintype "passive"))
      (node (ref "C59") (pin "2") (pinfunction "2_2") (pintype "passive"))
      (node (ref "C78") (pin "2") (pinfunction "2_2") (pintype "passive"))
      (node (ref "IC4") (pin "6") (pinfunction "IN_6") (pintype "passive"))
      (node (ref "IC5") (pin "3") (pinfunction "VIN_3") (pintype "passive"))
      (node (ref "IC6") (pin "3") (pinfunction "VIN_3") (pintype "passive"))
      (node (ref "IC6") (pin "5") (pinfunction "EN_5") (pintype "passive"))
      (node (ref "R50") (pin "2") (pinfunction "2_2") (pintype "passive"))
      (node (ref "R70") (pin "2") (pinfunction "2_2") (pintype "passive"))
      (node (ref "TP9") (pin "1") (pinfunction "TP2_1") (pintype "passive"))
    )
    (net (code "7") (name "GND") (class "Default")
      (node (ref "C100") (pin "1") (pinfunction "1_1") (pintype "passive"))
      (node (ref "C101") (pin "1") (pinfunction "1_1") (pintype "passive"))
      (node (ref "C102") (pin "1") (pinfunction "1_1") (pintype "passive"))
      (node (ref "C103") (pin "1") (pinfunction "1_1") (pintype "passive"))
      (node (ref "C104") (pin "1") (pinfunction "1_1") (pintype "passive"))
      (node (ref "C105") (pin "1") (pinfunction "1_1") (pintype "passive"))
      (node (ref "C106") (pin "1") (pinfunction "1_1") (pintype "passive"))
      (node (ref "C107") (pin "1") (pinfunction "1_1") (pintype "passive"))
      (node (ref "C108") (pin "1") (pinfunction "1_1") (pintype "passive"))
      (node (ref "C109") (pin "1") (pinfunction "1_1") (pintype "passive"))
      (node (ref "C111") (pin "1") (pinfunction "1_1") (pintype "passive"))
      (node (ref "C117") (pin "1") (pinfunction "1_1") (pintype "passive"))
      (node (ref "C118") (pin "1") (pinfunction "1_1") (pintype "passive"))
      (node (ref "C119") (pin "1") (pinfunction "1_1") (pintype "passive"))
      (node (ref "C120") (pin "1") (pinfunction "1_1") (pintype "passive"))
      (node (ref "C22") (pin "1") (pinfunction "1_1") (pintype "passive"))
      (node (ref "C59") (pin "1") (pinfunction "1_1") (pintype "passive"))
      (node (ref "C60") (pin "1") (pinfunction "1_1") (pintype "passive"))
      (node (ref "C62") (pin "1") (pinfunction "1_1") (pintype "passive"))
      (node (ref "C63") (pin "1") (pinfunction "1_1") (pintype "passive"))
      (node (ref "C64") (pin "1") (pinfunction "1_1") (pintype "passive"))
      (node (ref "C65") (pin "1") (pinfunction "1_1") (pintype "passive"))
      (node (ref "C66") (pin "1") (pinfunction "1_1") (pintype "passive"))
      (node (ref "C67") (pin "1") (pinfunction "1_1") (pintype "passive"))
      (node (ref "C68") (pin "1") (pinfunction "1_1") (pintype "passive"))
      (node (ref "C69") (pin "1") (pinfunction "1_1") (pintype "passive"))
      (node (ref "C70") (pin "1") (pinfunction "1_1") (pintype "passive"))
      (node (ref "C73") (pin "1") (pinfunction "1_1") (pintype "passive"))
      (node (ref "C74") (pin "1") (pinfunction "1_1") (pintype "passive"))
      (node (ref "C75") (pin "1") (pinfunction "1_1") (pintype "passive"))
      (node (ref "C76") (pin "1") (pinfunction "1_1") (pintype "passive"))
      (node (ref "C77") (pin "1") (pinfunction "1_1") (pintype "passive"))
      (node (ref "C78") (pin "1") (pinfunction "1_1") (pintype "passive"))
      (node (ref "C80") (pin "1") (pinfunction "1_1") (pintype "passive"))
      (node (ref "C81") (pin "1") (pinfunction "1_1") (pintype "passive"))
      (node (ref "C82") (pin "1") (pinfunction "1_1") (pintype "passive"))
      (node (ref "C83") (pin "1") (pinfunction "1_1") (pintype "passive"))
      (node (ref "C84") (pin "1") (pinfunction "1_1") (pintype "passive"))
      (node (ref "C85") (pin "1") (pinfunction "1_1") (pintype "passive"))
      (node (ref "C86") (pin "1") (pinfunction "1_1") (pintype "passive"))
      (node (ref "C87") (pin "1") (pinfunction "1_1") (pintype "passive"))
      (node (ref "C88") (pin "1") (pinfunction "1_1") (pintype "passive"))
      (node (ref "C89") (pin "1") (pinfunction "1_1") (pintype "passive"))
      (node (ref "C90") (pin "1") (pinfunction "1_1") (pintype "passive"))
      (node (ref "C91") (pin "1") (pinfunction "1_1") (pintype "passive"))
      (node (ref "C92") (pin "1") (pinfunction "1_1") (pintype "passive"))
      (node (ref "C93") (pin "1") (pinfunction "1_1") (pintype "passive"))
      (node (ref "C94") (pin "1") (pinfunction "1_1") (pintype "passive"))
      (node (ref "C95") (pin "1") (pinfunction "1_1") (pintype "passive"))
      (node (ref "C96") (pin "1") (pinfunction "1_1") (pintype "passive"))
      (node (ref "C97") (pin "1") (pinfunction "1_1") (pintype "passive"))
      (node (ref "C98") (pin "1") (pinfunction "1_1") (pintype "passive"))
      (node (ref "C99") (pin "1") (pinfunction "1_1") (pintype "passive"))
      (node (ref "D9") (pin "2") (pinfunction "2_2") (pintype "passive"))
      (node (ref "IC4") (pin "3") (pinfunction "GND_3") (pintype "passive"))
      (node (ref "IC4") (pin "7") (pinfunction "EP_7") (pintype "passive"))
      (node (ref "IC5") (pin "2") (pinfunction "GND_2") (pintype "passive"))
      (node (ref "IC6") (pin "2") (pinfunction "GND_2") (pintype "passive"))
      (node (ref "Q1") (pin "1") (pinfunction "S1_1") (pintype "passive"))
      (node (ref "Q1") (pin "4") (pinfunction "S2_4") (pintype "passive"))
      (node (ref "R2") (pin "1") (pinfunction "1_1") (pintype "passive"))
      (node (ref "R48") (pin "1") (pinfunction "1_1") (pintype "passive"))
      (node (ref "R83") (pin "1") (pinfunction "1_1") (pintype "passive"))
      (node (ref "TP10") (pin "1") (pinfunction "TP2_1") (pintype "passive"))
      (node (ref "U8") (pin "1") (pinfunction "GND_1") (pintype "passive"))
      (node (ref "U8") (pin "104") (pinfunction "GND_104") (pintype "passive"))
      (node (ref "U8") (pin "108") (pinfunction "GND_108") (pintype "passive"))
      (node (ref "U8") (pin "120") (pinfunction "GND_120") (pintype "passive"))
      (node (ref "U8") (pin "121") (pinfunction "GND_121") (pintype "passive"))
      (node (ref "U8") (pin "126") (pinfunction "GND_126") (pintype "passive"))
      (node (ref "U8") (pin "127") (pinfunction "GND_127") (pintype "passive"))
      (node (ref "U8") (pin "129") (pinfunction "GND_129") (pintype "passive"))
      (node (ref "U8") (pin "133") (pinfunction "GND_133") (pintype "passive"))
      (node (ref "U8") (pin "37") (pinfunction "GND_37") (pintype "passive"))
      (node (ref "U8") (pin "44") (pinfunction "GND_44") (pintype "passive"))
      (node (ref "U8") (pin "5") (pinfunction "GND_5") (pintype "passive"))
      (node (ref "U8") (pin "50") (pinfunction "GND_50") (pintype "passive"))
      (node (ref "U8") (pin "64") (pinfunction "GND_64") (pintype "passive"))
      (node (ref "U8") (pin "9") (pinfunction "GND_9") (pintype "passive"))
      (node (ref "U8") (pin "94") (pinfunction "GND_94") (pintype "passive"))
    )
    (net (code "8") (name "LVDS_VIO") (class "Default")
      (node (ref "C110") (pin "1") (pinfunction "1_1") (pintype "passive"))
      (node (ref "C111") (pin "2") (pinfunction "2_2") (pintype "passive"))
      (node (ref "C74") (pin "2") (pinfunction "2_2") (pintype "passive"))
      (node (ref "C75") (pin "2") (pinfunction "2_2") (pintype "passive"))
      (node (ref "C76") (pin "2") (pinfunction "2_2") (pintype "passive"))
      (node (ref "C77") (pin "2") (pinfunction "2_2") (pintype "passive"))
      (node (ref "C95") (pin "2") (pinfunction "2_2") (pintype "passive"))
      (node (ref "C97") (pin "2") (pinfunction "2_2") (pintype "passive"))
      (node (ref "IC4") (pin "1") (pinfunction "OUT_1") (pintype "passive"))
      (node (ref "R55") (pin "2") (pinfunction "2_2") (pintype "passive"))
      (node (ref "TP5") (pin "1") (pinfunction "TP2_1") (pintype "passive"))
      (node (ref "U8") (pin "51") (pinfunction "VCCIO4B_51") (pintype "passive"))
      (node (ref "U8") (pin "52") (pinfunction "VCCIO4B_52") (pintype "passive"))
      (node (ref "U8") (pin "62") (pinfunction "VCCIO4A_62") (pintype "passive"))
      (node (ref "U8") (pin "63") (pinfunction "VCCIO4A_63") (pintype "passive"))
    )
    (net (code "9") (name "Net-(D9-Pad1)") (class "Default")
      (node (ref "D9") (pin "1") (pinfunction "1_1") (pintype "passive"))
      (node (ref "R70") (pin "1") (pinfunction "1_1") (pintype "passive"))
    )
    (net (code "10") (name "Net-(IC4-FB)") (class "Default")
      (node (ref "C110") (pin "2") (pinfunction "2_2") (pintype "passive"))
      (node (ref "IC4") (pin "2") (pinfunction "FB_2") (pintype "passive"))
      (node (ref "R55") (pin "1") (pinfunction "1_1") (pintype "passive"))
      (node (ref "R56") (pin "2") (pinfunction "2_2") (pintype "passive"))
      (node (ref "R57") (pin "2") (pinfunction "2_2") (pintype "passive"))
      (node (ref "R83") (pin "2") (pinfunction "2_2") (pintype "passive"))
    )
    (net (code "11") (name "Net-(IC5-FB)") (class "Default")
      (node (ref "C79") (pin "1") (pinfunction "1_1") (pintype "passive"))
      (node (ref "IC5") (pin "1") (pinfunction "FB_1") (pintype "passive"))
      (node (ref "R2") (pin "2") (pinfunction "2_2") (pintype "passive"))
      (node (ref "R72") (pin "1") (pinfunction "1_1") (pintype "passive"))
    )
    (net (code "12") (name "Net-(IC5-SW)") (class "Default")
      (node (ref "IC5") (pin "4") (pinfunction "SW_4") (pintype "passive"))
      (node (ref "L1") (pin "1") (pinfunction "1_1") (pintype "passive"))
    )
    (net (code "13") (name "Net-(IC6-FB)") (class "Default")
      (node (ref "C61") (pin "1") (pinfunction "1_1") (pintype "passive"))
      (node (ref "IC6") (pin "1") (pinfunction "FB_1") (pintype "passive"))
      (node (ref "R46") (pin "1") (pinfunction "1_1") (pintype "passive"))
      (node (ref "R48") (pin "2") (pinfunction "2_2") (pintype "passive"))
    )
    (net (code "14") (name "Net-(IC6-SW)") (class "Default")
      (node (ref "IC6") (pin "4") (pinfunction "SW_4") (pintype "passive"))
      (node (ref "L2") (pin "1") (pinfunction "1_1") (pintype "passive"))
    )
    (net (code "15") (name "Net-(Q1A-D1)") (class "Default")
      (node (ref "Q1") (pin "6") (pinfunction "D1_6") (pintype "passive"))
      (node (ref "R56") (pin "1") (pinfunction "1_1") (pintype "passive"))
    )
    (net (code "16") (name "Net-(Q1A-G1)") (class "Default")
      (node (ref "Q1") (pin "2") (pinfunction "G1_2") (pintype "passive"))
      (node (ref "R53") (pin "1") (pinfunction "1_1") (pintype "passive"))
      (node (ref "R54") (pin "2") (pinfunction "2_2") (pintype "passive"))
    )
    (net (code "17") (name "Net-(Q1B-D2)") (class "Default")
      (node (ref "Q1") (pin "3") (pinfunction "D2_3") (pintype "passive"))
      (node (ref "R57") (pin "1") (pinfunction "1_1") (pintype "passive"))
    )
    (net (code "18") (name "Net-(Q1B-G2)") (class "Default")
      (node (ref "Q1") (pin "5") (pinfunction "G2_5") (pintype "passive"))
      (node (ref "R82") (pin "1") (pinfunction "1_1") (pintype "passive"))
      (node (ref "R84") (pin "2") (pinfunction "2_2") (pintype "passive"))
    )
    (net (code "19") (name "VBUS") (class "Default")
      (node (ref "TP6") (pin "1") (pinfunction "TP2_1") (pintype "passive"))
    )
    (net (code "20") (name "VCCA_BR") (class "Default")
      (node (ref "C67") (pin "2") (pinfunction "2_2") (pintype "passive"))
      (node (ref "FB11") (pin "2") (pinfunction "2_2") (pintype "passive"))
      (node (ref "U8") (pin "73") (pinfunction "VCCA_BR_73") (pintype "passive"))
    )
    (net (code "21") (name "VCCA_TL") (class "Default")
      (node (ref "C65") (pin "2") (pinfunction "2_2") (pintype "passive"))
      (node (ref "FB10") (pin "2") (pinfunction "2_2") (pintype "passive"))
      (node (ref "U8") (pin "2") (pinfunction "VCCA_TL_2") (pintype "passive"))
    )
    (net (code "22") (name "VCCA_TR") (class "Default")
      (node (ref "C63") (pin "2") (pinfunction "2_2") (pintype "passive"))
      (node (ref "FB9") (pin "2") (pinfunction "2_2") (pintype "passive"))
      (node (ref "U8") (pin "107") (pinfunction "VCCA_TR_107") (pintype "passive"))
    )
    (net (code "23") (name "unconnected-(IC4-DNC-Pad5)") (class "Default")
      (node (ref "IC4") (pin "5") (pinfunction "DNC_5") (pintype "passive+no_connect"))
    )
    (net (code "24") (name "unconnected-(IC5-NC{slash}PG-Pad6)") (class "Default")
      (node (ref "IC5") (pin "6") (pinfunction "NC/PG_6") (pintype "passive+no_connect"))
    )
  )
)
